# intel_realsense_d4xx_depth_cam_multi.net
KiCad netlist of a schematic drawn in EAGLE
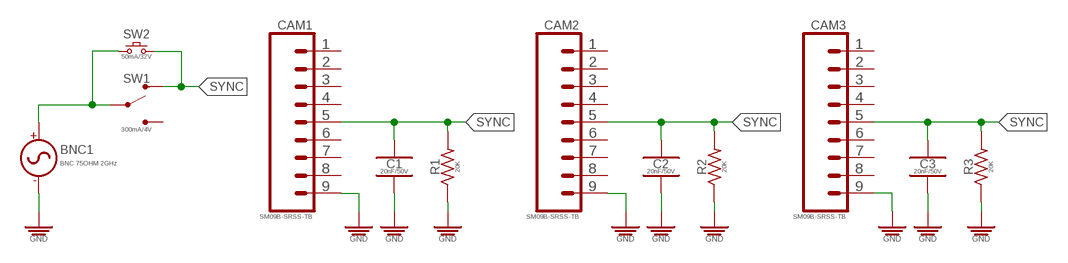
[diagram p0: schematic, sheet 1]

(export (version "E")
  (design (tool "Eeschema 10.0.6"))
  (components
    (comp (ref "BNC1")
      (value "BNC 75OHM 2GHz")
      (footprint "eagle-import:BNC_RA_1-1337543-0")
      (fields (field (name "MFR") "TE Connectivity AMP Connectors") (field (name "MPN") "1-1478032-0"))
      (libsource (lib "eagle-import") (part "BNC_CONNECTOR_PTH_75OHM_2GHZ"))
    )
    (comp (ref "C1")
      (value "20nF/50V")
      (footprint "eagle-import:CAPC1608X95")
      (fields (field (name "MFR") "TDK Corporation") (field (name "MPN") "C1608X8R1H223K080AA"))
      (libsource (lib "eagle-import") (part "22NF_CER_SMD-0603_50V-10%"))
    )
    (comp (ref "C2")
      (value "20nF/50V")
      (footprint "eagle-import:CAPC1608X95")
      (fields (field (name "MFR") "TDK Corporation") (field (name "MPN") "C1608X8R1H223K080AA"))
      (libsource (lib "eagle-import") (part "22NF_CER_SMD-0603_50V-10%"))
    )
    (comp (ref "C3")
      (value "20nF/50V")
      (footprint "eagle-import:CAPC1608X95")
      (fields (field (name "MFR") "TDK Corporation") (field (name "MPN") "C1608X8R1H223K080AA"))
      (libsource (lib "eagle-import") (part "22NF_CER_SMD-0603_50V-10%"))
    )
    (comp (ref "CAM1")
      (value "SM09B-SRSS-TB")
      (footprint "eagle-import:SM09B-SRSS-TB")
      (fields (field (name "MFR") "JST Sales America Inc.") (field (name "MPN") "SM09B-SRSS-TB(LF)(SN)"))
      (libsource (lib "eagle-import") (part "1X09_SM09B-SRSS-TB"))
    )
    (comp (ref "CAM2")
      (value "SM09B-SRSS-TB")
      (footprint "eagle-import:SM09B-SRSS-TB")
      (fields (field (name "MFR") "JST Sales America Inc.") (field (name "MPN") "SM09B-SRSS-TB(LF)(SN)"))
      (libsource (lib "eagle-import") (part "1X09_SM09B-SRSS-TB"))
    )
    (comp (ref "CAM3")
      (value "SM09B-SRSS-TB")
      (footprint "eagle-import:SM09B-SRSS-TB")
      (fields (field (name "MFR") "JST Sales America Inc.") (field (name "MPN") "SM09B-SRSS-TB(LF)(SN)"))
      (libsource (lib "eagle-import") (part "1X09_SM09B-SRSS-TB"))
    )
    (comp (ref "R1")
      (value "20K")
      (footprint "eagle-import:RESC1608X65_SMD-0603")
      (fields (field (name "MFR") "Panasonic Electronic Components") (field (name "MPN") "ERJ-3GEYJ203V"))
      (libsource (lib "eagle-import") (part "20KΩ_SMD-0603_1/10W-5%"))
    )
    (comp (ref "R2")
      (value "20K")
      (footprint "eagle-import:RESC1608X65_SMD-0603")
      (fields (field (name "MFR") "Panasonic Electronic Components") (field (name "MPN") "ERJ-3GEYJ203V"))
      (libsource (lib "eagle-import") (part "20KΩ_SMD-0603_1/10W-5%"))
    )
    (comp (ref "R3")
      (value "20K")
      (footprint "eagle-import:RESC1608X65_SMD-0603")
      (fields (field (name "MFR") "Panasonic Electronic Components") (field (name "MPN") "ERJ-3GEYJ203V"))
      (libsource (lib "eagle-import") (part "20KΩ_SMD-0603_1/10W-5%"))
    )
    (comp (ref "SW1")
      (value "300mA/4V")
      (footprint "eagle-import:SW_SLIDE_SPDT_RA_SMD_4V_300MA_6.7L-2.6W")
      (fields
        (field (name "MFR") "APEM Inc.")
        (field (name "MPN") "MA12RTR")
        (field (name "CREATOR") "MrSwirlyEyes")
      )
      (libsource (lib "eagle-import") (part "SWITCH_SPDT_RA_SMD_300MA-4V_6.7L-2.6W"))
    )
    (comp (ref "SW2")
      (value "50mA/32V")
      (footprint "eagle-import:BTN_MOMENTARY_SPDT-NO_L4.6-W2.8")
      (fields (field (name "MFR") "C&K") (field (name "MPN") "KMR211GLFS"))
      (libsource (lib "eagle-import") (part "SWITCH_MOMENTARY_SPST-NO_SMD_50MA-32V_L4.6-W2.8"))
    )
  )
  (nets
    (net (code "1") (name "GND") (class "Default")
      (node (ref "BNC1") (pin "-") (pinfunction "-_-") (pintype "bidirectional"))
      (node (ref "C1") (pin "2") (pinfunction "2_2") (pintype "passive"))
      (node (ref "C2") (pin "2") (pinfunction "2_2") (pintype "passive"))
      (node (ref "C3") (pin "2") (pinfunction "2_2") (pintype "passive"))
      (node (ref "CAM1") (pin "9") (pinfunction "9_9") (pintype "passive"))
      (node (ref "CAM2") (pin "9") (pinfunction "9_9") (pintype "passive"))
      (node (ref "CAM3") (pin "9") (pinfunction "9_9") (pintype "passive"))
      (node (ref "R1") (pin "1") (pinfunction "1_1") (pintype "passive"))
      (node (ref "R2") (pin "1") (pinfunction "1_1") (pintype "passive"))
      (node (ref "R3") (pin "1") (pinfunction "1_1") (pintype "passive"))
    )
    (net (code "2") (name "Net-(SW1-P)") (class "Default")
      (node (ref "BNC1") (pin "+") (pinfunction "+_+") (pintype "bidirectional"))
      (node (ref "SW1") (pin "2") (pinfunction "P_2") (pintype "passive"))
      (node (ref "SW2") (pin "2") (pinfunction "1_2") (pintype "passive"))
    )
    (net (code "3") (name "SYNC") (class "Default")
      (node (ref "C1") (pin "1") (pinfunction "1_1") (pintype "passive"))
      (node (ref "C2") (pin "1") (pinfunction "1_1") (pintype "passive"))
      (node (ref "C3") (pin "1") (pinfunction "1_1") (pintype "passive"))
      (node (ref "CAM1") (pin "5") (pinfunction "5_5") (pintype "passive"))
      (node (ref "CAM2") (pin "5") (pinfunction "5_5") (pintype "passive"))
      (node (ref "CAM3") (pin "5") (pinfunction "5_5") (pintype "passive"))
      (node (ref "R1") (pin "2") (pinfunction "2_2") (pintype "passive"))
      (node (ref "R2") (pin "2") (pinfunction "2_2") (pintype "passive"))
      (node (ref "R3") (pin "2") (pinfunction "2_2") (pintype "passive"))
      (node (ref "SW1") (pin "1") (pinfunction "S1_1") (pintype "passive"))
      (node (ref "SW2") (pin "3") (pinfunction "2_3") (pintype "passive"))
    )
    (net (code "4") (name "unconnected-(CAM1-Pad1)") (class "Default")
      (node (ref "CAM1") (pin "1") (pinfunction "1_1") (pintype "passive"))
    )
    (net (code "5") (name "unconnected-(CAM1-Pad2)") (class "Default")
      (node (ref "CAM1") (pin "2") (pinfunction "2_2") (pintype "passive"))
    )
    (net (code "6") (name "unconnected-(CAM1-Pad3)") (class "Default")
      (node (ref "CAM1") (pin "3") (pinfunction "3_3") (pintype "passive"))
    )
    (net (code "7") (name "unconnected-(CAM1-Pad4)") (class "Default")
      (node (ref "CAM1") (pin "4") (pinfunction "4_4") (pintype "passive"))
    )
    (net (code "8") (name "unconnected-(CAM1-Pad6)") (class "Default")
      (node (ref "CAM1") (pin "6") (pinfunction "6_6") (pintype "passive"))
    )
    (net (code "9") (name "unconnected-(CAM1-Pad7)") (class "Default")
      (node (ref "CAM1") (pin "7") (pinfunction "7_7") (pintype "passive"))
    )
    (net (code "10") (name "unconnected-(CAM1-Pad8)") (class "Default")
      (node (ref "CAM1") (pin "8") (pinfunction "8_8") (pintype "passive"))
    )
    (net (code "11") (name "unconnected-(CAM2-Pad1)") (class "Default")
      (node (ref "CAM2") (pin "1") (pinfunction "1_1") (pintype "passive"))
    )
    (net (code "12") (name "unconnected-(CAM2-Pad2)") (class "Default")
      (node (ref "CAM2") (pin "2") (pinfunction "2_2") (pintype "passive"))
    )
    (net (code "13") (name "unconnected-(CAM2-Pad3)") (class "Default")
      (node (ref "CAM2") (pin "3") (pinfunction "3_3") (pintype "passive"))
    )
    (net (code "14") (name "unconnected-(CAM2-Pad4)") (class "Default")
      (node (ref "CAM2") (pin "4") (pinfunction "4_4") (pintype "passive"))
    )
    (net (code "15") (name "unconnected-(CAM2-Pad6)") (class "Default")
      (node (ref "CAM2") (pin "6") (pinfunction "6_6") (pintype "passive"))
    )
    (net (code "16") (name "unconnected-(CAM2-Pad7)") (class "Default")
      (node (ref "CAM2") (pin "7") (pinfunction "7_7") (pintype "passive"))
    )
    (net (code "17") (name "unconnected-(CAM2-Pad8)") (class "Default")
      (node (ref "CAM2") (pin "8") (pinfunction "8_8") (pintype "passive"))
    )
    (net (code "18") (name "unconnected-(CAM3-Pad1)") (class "Default")
      (node (ref "CAM3") (pin "1") (pinfunction "1_1") (pintype "passive"))
    )
    (net (code "19") (name "unconnected-(CAM3-Pad2)") (class "Default")
      (node (ref "CAM3") (pin "2") (pinfunction "2_2") (pintype "passive"))
    )
    (net (code "20") (name "unconnected-(CAM3-Pad3)") (class "Default")
      (node (ref "CAM3") (pin "3") (pinfunction "3_3") (pintype "passive"))
    )
    (net (code "21") (name "unconnected-(CAM3-Pad4)") (class "Default")
      (node (ref "CAM3") (pin "4") (pinfunction "4_4") (pintype "passive"))
    )
    (net (code "22") (name "unconnected-(CAM3-Pad6)") (class "Default")
      (node (ref "CAM3") (pin "6") (pinfunction "6_6") (pintype "passive"))
    )
    (net (code "23") (name "unconnected-(CAM3-Pad7)") (class "Default")
      (node (ref "CAM3") (pin "7") (pinfunction "7_7") (pintype "passive"))
    )
    (net (code "24") (name "unconnected-(CAM3-Pad8)") (class "Default")
      (node (ref "CAM3") (pin "8") (pinfunction "8_8") (pintype "passive"))
    )
    (net (code "25") (name "unconnected-(SW1-S2-Pad3)") (class "Default")
      (node (ref "SW1") (pin "3") (pinfunction "S2_3") (pintype "passive"))
    )
  )
)
